# LEDMatrix.net
KiCad netlist of a schematic drawn in Altium Designer
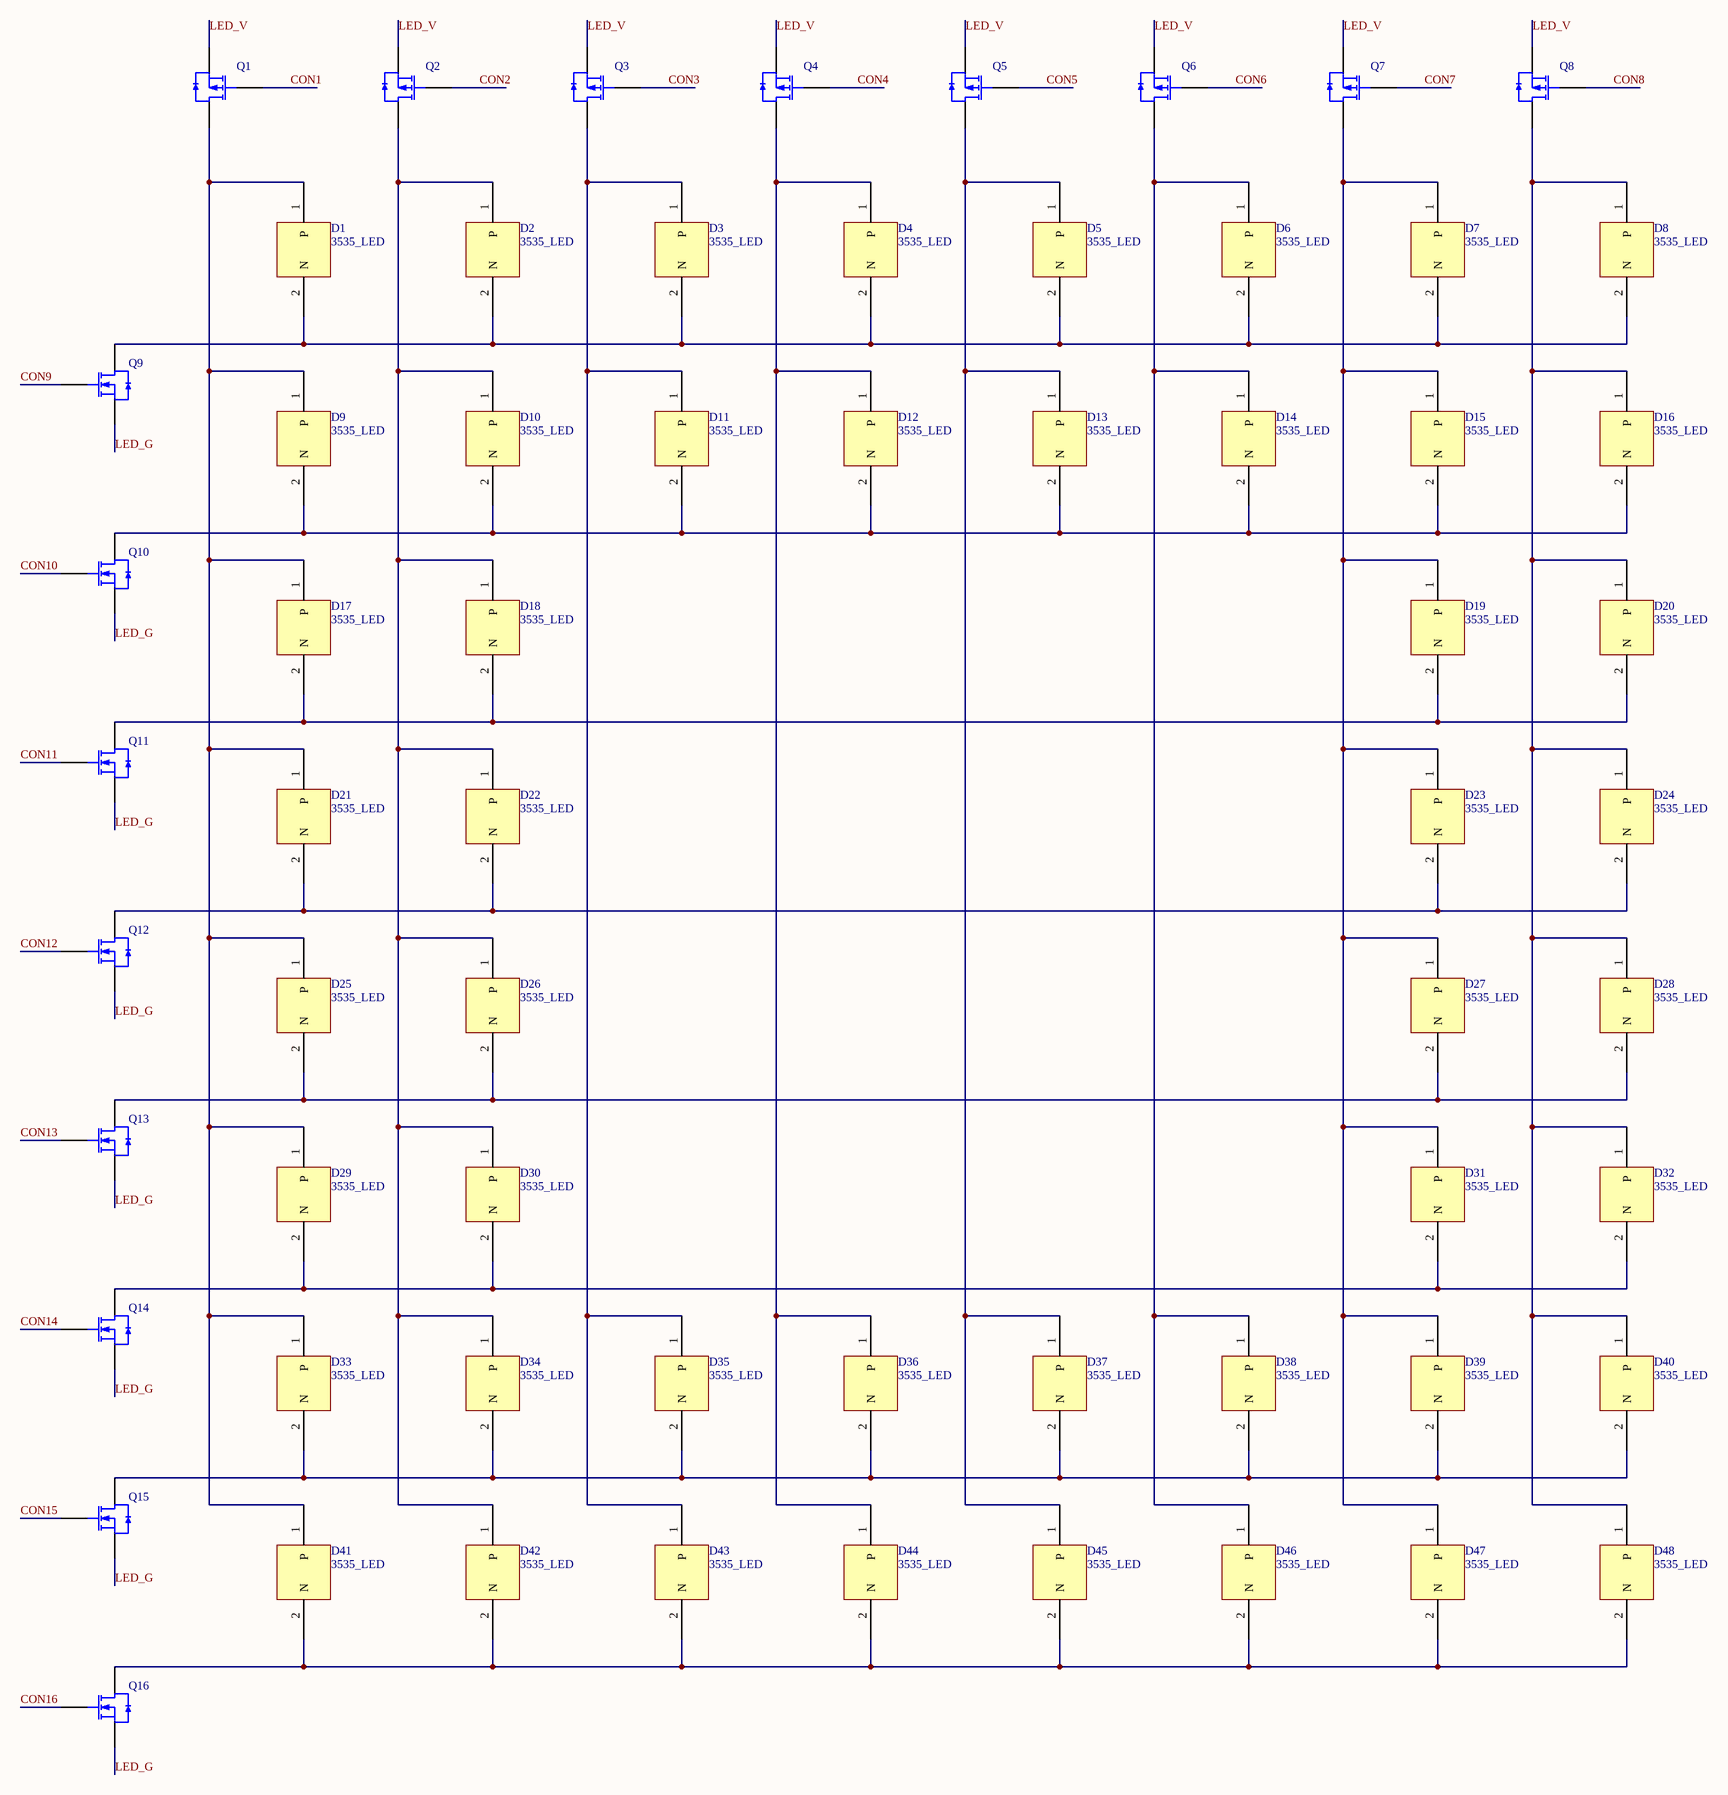
[diagram p0: LEDMatrix.SchDoc]

(export (version "E")
  (design (tool "Eeschema 10.0.6"))
  (components
    (comp (ref "D1") (value "3535_LED") (footprint "3535_LED") (libsource (lib "myself") (part "3535_LED")))
    (comp (ref "D2") (value "3535_LED") (footprint "3535_LED") (libsource (lib "myself") (part "3535_LED")))
    (comp (ref "D3") (value "3535_LED") (footprint "3535_LED") (libsource (lib "myself") (part "3535_LED")))
    (comp (ref "D4") (value "3535_LED") (footprint "3535_LED") (libsource (lib "myself") (part "3535_LED")))
    (comp (ref "D5") (value "3535_LED") (footprint "3535_LED") (libsource (lib "myself") (part "3535_LED")))
    (comp (ref "D6") (value "3535_LED") (footprint "3535_LED") (libsource (lib "myself") (part "3535_LED")))
    (comp (ref "D7") (value "3535_LED") (footprint "3535_LED") (libsource (lib "myself") (part "3535_LED")))
    (comp (ref "D8") (value "3535_LED") (footprint "3535_LED") (libsource (lib "myself") (part "3535_LED")))
    (comp (ref "D9") (value "3535_LED") (footprint "3535_LED") (libsource (lib "myself") (part "3535_LED")))
    (comp (ref "D10") (value "3535_LED") (footprint "3535_LED") (libsource (lib "myself") (part "3535_LED")))
    (comp (ref "D11") (value "3535_LED") (footprint "3535_LED") (libsource (lib "myself") (part "3535_LED")))
    (comp (ref "D12") (value "3535_LED") (footprint "3535_LED") (libsource (lib "myself") (part "3535_LED")))
    (comp (ref "D13") (value "3535_LED") (footprint "3535_LED") (libsource (lib "myself") (part "3535_LED")))
    (comp (ref "D14") (value "3535_LED") (footprint "3535_LED") (libsource (lib "myself") (part "3535_LED")))
    (comp (ref "D15") (value "3535_LED") (footprint "3535_LED") (libsource (lib "myself") (part "3535_LED")))
    (comp (ref "D16") (value "3535_LED") (footprint "3535_LED") (libsource (lib "myself") (part "3535_LED")))
    (comp (ref "D17") (value "3535_LED") (footprint "3535_LED") (libsource (lib "myself") (part "3535_LED")))
    (comp (ref "D18") (value "3535_LED") (footprint "3535_LED") (libsource (lib "myself") (part "3535_LED")))
    (comp (ref "D19") (value "3535_LED") (footprint "3535_LED") (libsource (lib "myself") (part "3535_LED")))
    (comp (ref "D20") (value "3535_LED") (footprint "3535_LED") (libsource (lib "myself") (part "3535_LED")))
    (comp (ref "D21") (value "3535_LED") (footprint "3535_LED") (libsource (lib "myself") (part "3535_LED")))
    (comp (ref "D22") (value "3535_LED") (footprint "3535_LED") (libsource (lib "myself") (part "3535_LED")))
    (comp (ref "D23") (value "3535_LED") (footprint "3535_LED") (libsource (lib "myself") (part "3535_LED")))
    (comp (ref "D24") (value "3535_LED") (footprint "3535_LED") (libsource (lib "myself") (part "3535_LED")))
    (comp (ref "D25") (value "3535_LED") (footprint "3535_LED") (libsource (lib "myself") (part "3535_LED")))
    (comp (ref "D26") (value "3535_LED") (footprint "3535_LED") (libsource (lib "myself") (part "3535_LED")))
    (comp (ref "D27") (value "3535_LED") (footprint "3535_LED") (libsource (lib "myself") (part "3535_LED")))
    (comp (ref "D28") (value "3535_LED") (footprint "3535_LED") (libsource (lib "myself") (part "3535_LED")))
    (comp (ref "D29") (value "3535_LED") (footprint "3535_LED") (libsource (lib "myself") (part "3535_LED")))
    (comp (ref "D30") (value "3535_LED") (footprint "3535_LED") (libsource (lib "myself") (part "3535_LED")))
    (comp (ref "D31") (value "3535_LED") (footprint "3535_LED") (libsource (lib "myself") (part "3535_LED")))
    (comp (ref "D32") (value "3535_LED") (footprint "3535_LED") (libsource (lib "myself") (part "3535_LED")))
    (comp (ref "D33") (value "3535_LED") (footprint "3535_LED") (libsource (lib "myself") (part "3535_LED")))
    (comp (ref "D34") (value "3535_LED") (footprint "3535_LED") (libsource (lib "myself") (part "3535_LED")))
    (comp (ref "D35") (value "3535_LED") (footprint "3535_LED") (libsource (lib "myself") (part "3535_LED")))
    (comp (ref "D36") (value "3535_LED") (footprint "3535_LED") (libsource (lib "myself") (part "3535_LED")))
    (comp (ref "D37") (value "3535_LED") (footprint "3535_LED") (libsource (lib "myself") (part "3535_LED")))
    (comp (ref "D38") (value "3535_LED") (footprint "3535_LED") (libsource (lib "myself") (part "3535_LED")))
    (comp (ref "D39") (value "3535_LED") (footprint "3535_LED") (libsource (lib "myself") (part "3535_LED")))
    (comp (ref "D40") (value "3535_LED") (footprint "3535_LED") (libsource (lib "myself") (part "3535_LED")))
    (comp (ref "D41") (value "3535_LED") (footprint "3535_LED") (libsource (lib "myself") (part "3535_LED")))
    (comp (ref "D42") (value "3535_LED") (footprint "3535_LED") (libsource (lib "myself") (part "3535_LED")))
    (comp (ref "D43") (value "3535_LED") (footprint "3535_LED") (libsource (lib "myself") (part "3535_LED")))
    (comp (ref "D44") (value "3535_LED") (footprint "3535_LED") (libsource (lib "myself") (part "3535_LED")))
    (comp (ref "D45") (value "3535_LED") (footprint "3535_LED") (libsource (lib "myself") (part "3535_LED")))
    (comp (ref "D46") (value "3535_LED") (footprint "3535_LED") (libsource (lib "myself") (part "3535_LED")))
    (comp (ref "D47") (value "3535_LED") (footprint "3535_LED") (libsource (lib "myself") (part "3535_LED")))
    (comp (ref "D48") (value "3535_LED") (footprint "3535_LED") (libsource (lib "myself") (part "3535_LED")))
    (comp (ref "Q1")
      (value "AO3401A P道沟 X13A15 SOT-23")
      (footprint "LC-SOT-23-3L")
      (description "MOS(场效应管)")
      (libsource (lib "sfzself") (part "AO3401A P道沟 X13A15 SOT-23"))
    )
    (comp (ref "Q2")
      (value "AO3401A P道沟 X13A15 SOT-23")
      (footprint "LC-SOT-23-3L")
      (description "MOS(场效应管)")
      (libsource (lib "sfzself") (part "AO3401A P道沟 X13A15 SOT-23"))
    )
    (comp (ref "Q3")
      (value "AO3401A P道沟 X13A15 SOT-23")
      (footprint "LC-SOT-23-3L")
      (description "MOS(场效应管)")
      (libsource (lib "sfzself") (part "AO3401A P道沟 X13A15 SOT-23"))
    )
    (comp (ref "Q4")
      (value "AO3401A P道沟 X13A15 SOT-23")
      (footprint "LC-SOT-23-3L")
      (description "MOS(场效应管)")
      (libsource (lib "sfzself") (part "AO3401A P道沟 X13A15 SOT-23"))
    )
    (comp (ref "Q5")
      (value "AO3401A P道沟 X13A15 SOT-23")
      (footprint "LC-SOT-23-3L")
      (description "MOS(场效应管)")
      (libsource (lib "sfzself") (part "AO3401A P道沟 X13A15 SOT-23"))
    )
    (comp (ref "Q6")
      (value "AO3401A P道沟 X13A15 SOT-23")
      (footprint "LC-SOT-23-3L")
      (description "MOS(场效应管)")
      (libsource (lib "sfzself") (part "AO3401A P道沟 X13A15 SOT-23"))
    )
    (comp (ref "Q7")
      (value "AO3401A P道沟 X13A15 SOT-23")
      (footprint "LC-SOT-23-3L")
      (description "MOS(场效应管)")
      (libsource (lib "sfzself") (part "AO3401A P道沟 X13A15 SOT-23"))
    )
    (comp (ref "Q8")
      (value "AO3401A P道沟 X13A15 SOT-23")
      (footprint "LC-SOT-23-3L")
      (description "MOS(场效应管)")
      (libsource (lib "sfzself") (part "AO3401A P道沟 X13A15 SOT-23"))
    )
    (comp (ref "Q9")
      (value "AO3400A N道沟 X0YV1T SOT-23")
      (footprint "SOT-23-3L")
      (description "MOS(场效应管)")
      (libsource (lib "Miscellaneous Devices LC") (part "AO3400A N道沟 X0YV1T SOT-23"))
    )
    (comp (ref "Q10")
      (value "AO3400A N道沟 X0YV1T SOT-23")
      (footprint "SOT-23-3L")
      (description "MOS(场效应管)")
      (libsource (lib "Miscellaneous Devices LC") (part "AO3400A N道沟 X0YV1T SOT-23"))
    )
    (comp (ref "Q11")
      (value "AO3400A N道沟 X0YV1T SOT-23")
      (footprint "SOT-23-3L")
      (description "MOS(场效应管)")
      (libsource (lib "Miscellaneous Devices LC") (part "AO3400A N道沟 X0YV1T SOT-23"))
    )
    (comp (ref "Q12")
      (value "AO3400A N道沟 X0YV1T SOT-23")
      (footprint "SOT-23-3L")
      (description "MOS(场效应管)")
      (libsource (lib "Miscellaneous Devices LC") (part "AO3400A N道沟 X0YV1T SOT-23"))
    )
    (comp (ref "Q13")
      (value "AO3400A N道沟 X0YV1T SOT-23")
      (footprint "SOT-23-3L")
      (description "MOS(场效应管)")
      (libsource (lib "Miscellaneous Devices LC") (part "AO3400A N道沟 X0YV1T SOT-23"))
    )
    (comp (ref "Q14")
      (value "AO3400A N道沟 X0YV1T SOT-23")
      (footprint "SOT-23-3L")
      (description "MOS(场效应管)")
      (libsource (lib "Miscellaneous Devices LC") (part "AO3400A N道沟 X0YV1T SOT-23"))
    )
    (comp (ref "Q15")
      (value "AO3400A N道沟 X0YV1T SOT-23")
      (footprint "SOT-23-3L")
      (description "MOS(场效应管)")
      (libsource (lib "Miscellaneous Devices LC") (part "AO3400A N道沟 X0YV1T SOT-23"))
    )
    (comp (ref "Q16")
      (value "AO3400A N道沟 X0YV1T SOT-23")
      (footprint "SOT-23-3L")
      (description "MOS(场效应管)")
      (libsource (lib "Miscellaneous Devices LC") (part "AO3400A N道沟 X0YV1T SOT-23"))
    )
  )
  (nets
    (net (code "1") (name "/CON1") (class "Default")
      (node (ref "Q1") (pin "1") (pinfunction "G_1") (pintype "passive"))
    )
    (net (code "2") (name "/CON2") (class "Default")
      (node (ref "Q2") (pin "1") (pinfunction "G_1") (pintype "passive"))
    )
    (net (code "3") (name "/CON3") (class "Default")
      (node (ref "Q3") (pin "1") (pinfunction "G_1") (pintype "passive"))
    )
    (net (code "4") (name "/CON4") (class "Default")
      (node (ref "Q4") (pin "1") (pinfunction "G_1") (pintype "passive"))
    )
    (net (code "5") (name "/CON5") (class "Default")
      (node (ref "Q5") (pin "1") (pinfunction "G_1") (pintype "passive"))
    )
    (net (code "6") (name "/CON6") (class "Default")
      (node (ref "Q6") (pin "1") (pinfunction "G_1") (pintype "passive"))
    )
    (net (code "7") (name "/CON7") (class "Default")
      (node (ref "Q7") (pin "1") (pinfunction "G_1") (pintype "passive"))
    )
    (net (code "8") (name "/CON8") (class "Default")
      (node (ref "Q8") (pin "1") (pinfunction "G_1") (pintype "passive"))
    )
    (net (code "9") (name "/CON9") (class "Default")
      (node (ref "Q9") (pin "1") (pinfunction "G_1") (pintype "passive"))
    )
    (net (code "10") (name "/CON10") (class "Default")
      (node (ref "Q10") (pin "1") (pinfunction "G_1") (pintype "passive"))
    )
    (net (code "11") (name "/CON11") (class "Default")
      (node (ref "Q11") (pin "1") (pinfunction "G_1") (pintype "passive"))
    )
    (net (code "12") (name "/CON12") (class "Default")
      (node (ref "Q12") (pin "1") (pinfunction "G_1") (pintype "passive"))
    )
    (net (code "13") (name "/CON13") (class "Default")
      (node (ref "Q13") (pin "1") (pinfunction "G_1") (pintype "passive"))
    )
    (net (code "14") (name "/CON14") (class "Default")
      (node (ref "Q14") (pin "1") (pinfunction "G_1") (pintype "passive"))
    )
    (net (code "15") (name "/CON15") (class "Default")
      (node (ref "Q15") (pin "1") (pinfunction "G_1") (pintype "passive"))
    )
    (net (code "16") (name "/CON16") (class "Default")
      (node (ref "Q16") (pin "1") (pinfunction "G_1") (pintype "passive"))
    )
    (net (code "17") (name "/LED_G") (class "Default")
      (node (ref "Q10") (pin "2") (pinfunction "S_2") (pintype "passive"))
      (node (ref "Q11") (pin "2") (pinfunction "S_2") (pintype "passive"))
      (node (ref "Q12") (pin "2") (pinfunction "S_2") (pintype "passive"))
      (node (ref "Q13") (pin "2") (pinfunction "S_2") (pintype "passive"))
      (node (ref "Q14") (pin "2") (pinfunction "S_2") (pintype "passive"))
      (node (ref "Q15") (pin "2") (pinfunction "S_2") (pintype "passive"))
      (node (ref "Q16") (pin "2") (pinfunction "S_2") (pintype "passive"))
      (node (ref "Q9") (pin "2") (pinfunction "S_2") (pintype "passive"))
    )
    (net (code "18") (name "/LED_V") (class "Default")
      (node (ref "Q1") (pin "2") (pinfunction "S_2") (pintype "passive"))
      (node (ref "Q2") (pin "2") (pinfunction "S_2") (pintype "passive"))
      (node (ref "Q3") (pin "2") (pinfunction "S_2") (pintype "passive"))
      (node (ref "Q4") (pin "2") (pinfunction "S_2") (pintype "passive"))
      (node (ref "Q5") (pin "2") (pinfunction "S_2") (pintype "passive"))
      (node (ref "Q6") (pin "2") (pinfunction "S_2") (pintype "passive"))
      (node (ref "Q7") (pin "2") (pinfunction "S_2") (pintype "passive"))
      (node (ref "Q8") (pin "2") (pinfunction "S_2") (pintype "passive"))
    )
    (net (code "19") (name "Net-(D1-N)") (class "Default")
      (node (ref "D1") (pin "2") (pinfunction "N_2") (pintype "passive"))
      (node (ref "D2") (pin "2") (pinfunction "N_2") (pintype "passive"))
      (node (ref "D3") (pin "2") (pinfunction "N_2") (pintype "passive"))
      (node (ref "D4") (pin "2") (pinfunction "N_2") (pintype "passive"))
      (node (ref "D5") (pin "2") (pinfunction "N_2") (pintype "passive"))
      (node (ref "D6") (pin "2") (pinfunction "N_2") (pintype "passive"))
      (node (ref "D7") (pin "2") (pinfunction "N_2") (pintype "passive"))
      (node (ref "D8") (pin "2") (pinfunction "N_2") (pintype "passive"))
      (node (ref "Q9") (pin "3") (pinfunction "D_3") (pintype "passive"))
    )
    (net (code "20") (name "Net-(D1-P)") (class "Default")
      (node (ref "D1") (pin "1") (pinfunction "P_1") (pintype "passive"))
      (node (ref "D17") (pin "1") (pinfunction "P_1") (pintype "passive"))
      (node (ref "D21") (pin "1") (pinfunction "P_1") (pintype "passive"))
      (node (ref "D25") (pin "1") (pinfunction "P_1") (pintype "passive"))
      (node (ref "D29") (pin "1") (pinfunction "P_1") (pintype "passive"))
      (node (ref "D33") (pin "1") (pinfunction "P_1") (pintype "passive"))
      (node (ref "D41") (pin "1") (pinfunction "P_1") (pintype "passive"))
      (node (ref "D9") (pin "1") (pinfunction "P_1") (pintype "passive"))
      (node (ref "Q1") (pin "3") (pinfunction "D_3") (pintype "passive"))
    )
    (net (code "21") (name "Net-(D10-N)") (class "Default")
      (node (ref "D10") (pin "2") (pinfunction "N_2") (pintype "passive"))
      (node (ref "D11") (pin "2") (pinfunction "N_2") (pintype "passive"))
      (node (ref "D12") (pin "2") (pinfunction "N_2") (pintype "passive"))
      (node (ref "D13") (pin "2") (pinfunction "N_2") (pintype "passive"))
      (node (ref "D14") (pin "2") (pinfunction "N_2") (pintype "passive"))
      (node (ref "D15") (pin "2") (pinfunction "N_2") (pintype "passive"))
      (node (ref "D16") (pin "2") (pinfunction "N_2") (pintype "passive"))
      (node (ref "D9") (pin "2") (pinfunction "N_2") (pintype "passive"))
      (node (ref "Q10") (pin "3") (pinfunction "D_3") (pintype "passive"))
    )
    (net (code "22") (name "Net-(D10-P)") (class "Default")
      (node (ref "D10") (pin "1") (pinfunction "P_1") (pintype "passive"))
      (node (ref "D18") (pin "1") (pinfunction "P_1") (pintype "passive"))
      (node (ref "D2") (pin "1") (pinfunction "P_1") (pintype "passive"))
      (node (ref "D22") (pin "1") (pinfunction "P_1") (pintype "passive"))
      (node (ref "D26") (pin "1") (pinfunction "P_1") (pintype "passive"))
      (node (ref "D30") (pin "1") (pinfunction "P_1") (pintype "passive"))
      (node (ref "D34") (pin "1") (pinfunction "P_1") (pintype "passive"))
      (node (ref "D42") (pin "1") (pinfunction "P_1") (pintype "passive"))
      (node (ref "Q2") (pin "3") (pinfunction "D_3") (pintype "passive"))
    )
    (net (code "23") (name "Net-(D11-P)") (class "Default")
      (node (ref "D11") (pin "1") (pinfunction "P_1") (pintype "passive"))
      (node (ref "D3") (pin "1") (pinfunction "P_1") (pintype "passive"))
      (node (ref "D35") (pin "1") (pinfunction "P_1") (pintype "passive"))
      (node (ref "D43") (pin "1") (pinfunction "P_1") (pintype "passive"))
      (node (ref "Q3") (pin "3") (pinfunction "D_3") (pintype "passive"))
    )
    (net (code "24") (name "Net-(D12-P)") (class "Default")
      (node (ref "D12") (pin "1") (pinfunction "P_1") (pintype "passive"))
      (node (ref "D36") (pin "1") (pinfunction "P_1") (pintype "passive"))
      (node (ref "D4") (pin "1") (pinfunction "P_1") (pintype "passive"))
      (node (ref "D44") (pin "1") (pinfunction "P_1") (pintype "passive"))
      (node (ref "Q4") (pin "3") (pinfunction "D_3") (pintype "passive"))
    )
    (net (code "25") (name "Net-(D13-P)") (class "Default")
      (node (ref "D13") (pin "1") (pinfunction "P_1") (pintype "passive"))
      (node (ref "D37") (pin "1") (pinfunction "P_1") (pintype "passive"))
      (node (ref "D45") (pin "1") (pinfunction "P_1") (pintype "passive"))
      (node (ref "D5") (pin "1") (pinfunction "P_1") (pintype "passive"))
      (node (ref "Q5") (pin "3") (pinfunction "D_3") (pintype "passive"))
    )
    (net (code "26") (name "Net-(D14-P)") (class "Default")
      (node (ref "D14") (pin "1") (pinfunction "P_1") (pintype "passive"))
      (node (ref "D38") (pin "1") (pinfunction "P_1") (pintype "passive"))
      (node (ref "D46") (pin "1") (pinfunction "P_1") (pintype "passive"))
      (node (ref "D6") (pin "1") (pinfunction "P_1") (pintype "passive"))
      (node (ref "Q6") (pin "3") (pinfunction "D_3") (pintype "passive"))
    )
    (net (code "27") (name "Net-(D15-P)") (class "Default")
      (node (ref "D15") (pin "1") (pinfunction "P_1") (pintype "passive"))
      (node (ref "D19") (pin "1") (pinfunction "P_1") (pintype "passive"))
      (node (ref "D23") (pin "1") (pinfunction "P_1") (pintype "passive"))
      (node (ref "D27") (pin "1") (pinfunction "P_1") (pintype "passive"))
      (node (ref "D31") (pin "1") (pinfunction "P_1") (pintype "passive"))
      (node (ref "D39") (pin "1") (pinfunction "P_1") (pintype "passive"))
      (node (ref "D47") (pin "1") (pinfunction "P_1") (pintype "passive"))
      (node (ref "D7") (pin "1") (pinfunction "P_1") (pintype "passive"))
      (node (ref "Q7") (pin "3") (pinfunction "D_3") (pintype "passive"))
    )
    (net (code "28") (name "Net-(D16-P)") (class "Default")
      (node (ref "D16") (pin "1") (pinfunction "P_1") (pintype "passive"))
      (node (ref "D20") (pin "1") (pinfunction "P_1") (pintype "passive"))
      (node (ref "D24") (pin "1") (pinfunction "P_1") (pintype "passive"))
      (node (ref "D28") (pin "1") (pinfunction "P_1") (pintype "passive"))
      (node (ref "D32") (pin "1") (pinfunction "P_1") (pintype "passive"))
      (node (ref "D40") (pin "1") (pinfunction "P_1") (pintype "passive"))
      (node (ref "D48") (pin "1") (pinfunction "P_1") (pintype "passive"))
      (node (ref "D8") (pin "1") (pinfunction "P_1") (pintype "passive"))
      (node (ref "Q8") (pin "3") (pinfunction "D_3") (pintype "passive"))
    )
    (net (code "29") (name "Net-(D17-N)") (class "Default")
      (node (ref "D17") (pin "2") (pinfunction "N_2") (pintype "passive"))
      (node (ref "D18") (pin "2") (pinfunction "N_2") (pintype "passive"))
      (node (ref "D19") (pin "2") (pinfunction "N_2") (pintype "passive"))
      (node (ref "D20") (pin "2") (pinfunction "N_2") (pintype "passive"))
      (node (ref "Q11") (pin "3") (pinfunction "D_3") (pintype "passive"))
    )
    (net (code "30") (name "Net-(D21-N)") (class "Default")
      (node (ref "D21") (pin "2") (pinfunction "N_2") (pintype "passive"))
      (node (ref "D22") (pin "2") (pinfunction "N_2") (pintype "passive"))
      (node (ref "D23") (pin "2") (pinfunction "N_2") (pintype "passive"))
      (node (ref "D24") (pin "2") (pinfunction "N_2") (pintype "passive"))
      (node (ref "Q12") (pin "3") (pinfunction "D_3") (pintype "passive"))
    )
    (net (code "31") (name "Net-(D25-N)") (class "Default")
      (node (ref "D25") (pin "2") (pinfunction "N_2") (pintype "passive"))
      (node (ref "D26") (pin "2") (pinfunction "N_2") (pintype "passive"))
      (node (ref "D27") (pin "2") (pinfunction "N_2") (pintype "passive"))
      (node (ref "D28") (pin "2") (pinfunction "N_2") (pintype "passive"))
      (node (ref "Q13") (pin "3") (pinfunction "D_3") (pintype "passive"))
    )
    (net (code "32") (name "Net-(D29-N)") (class "Default")
      (node (ref "D29") (pin "2") (pinfunction "N_2") (pintype "passive"))
      (node (ref "D30") (pin "2") (pinfunction "N_2") (pintype "passive"))
      (node (ref "D31") (pin "2") (pinfunction "N_2") (pintype "passive"))
      (node (ref "D32") (pin "2") (pinfunction "N_2") (pintype "passive"))
      (node (ref "Q14") (pin "3") (pinfunction "D_3") (pintype "passive"))
    )
    (net (code "33") (name "Net-(D33-N)") (class "Default")
      (node (ref "D33") (pin "2") (pinfunction "N_2") (pintype "passive"))
      (node (ref "D34") (pin "2") (pinfunction "N_2") (pintype "passive"))
      (node (ref "D35") (pin "2") (pinfunction "N_2") (pintype "passive"))
      (node (ref "D36") (pin "2") (pinfunction "N_2") (pintype "passive"))
      (node (ref "D37") (pin "2") (pinfunction "N_2") (pintype "passive"))
      (node (ref "D38") (pin "2") (pinfunction "N_2") (pintype "passive"))
      (node (ref "D39") (pin "2") (pinfunction "N_2") (pintype "passive"))
      (node (ref "D40") (pin "2") (pinfunction "N_2") (pintype "passive"))
      (node (ref "Q15") (pin "3") (pinfunction "D_3") (pintype "passive"))
    )
    (net (code "34") (name "Net-(D41-N)") (class "Default")
      (node (ref "D41") (pin "2") (pinfunction "N_2") (pintype "passive"))
      (node (ref "D42") (pin "2") (pinfunction "N_2") (pintype "passive"))
      (node (ref "D43") (pin "2") (pinfunction "N_2") (pintype "passive"))
      (node (ref "D44") (pin "2") (pinfunction "N_2") (pintype "passive"))
      (node (ref "D45") (pin "2") (pinfunction "N_2") (pintype "passive"))
      (node (ref "D46") (pin "2") (pinfunction "N_2") (pintype "passive"))
      (node (ref "D47") (pin "2") (pinfunction "N_2") (pintype "passive"))
      (node (ref "D48") (pin "2") (pinfunction "N_2") (pintype "passive"))
      (node (ref "Q16") (pin "3") (pinfunction "D_3") (pintype "passive"))
    )
  )
)
